# SCH_EspNowHub_2023-01-29.net
KiCad netlist of a schematic drawn in EasyEDA
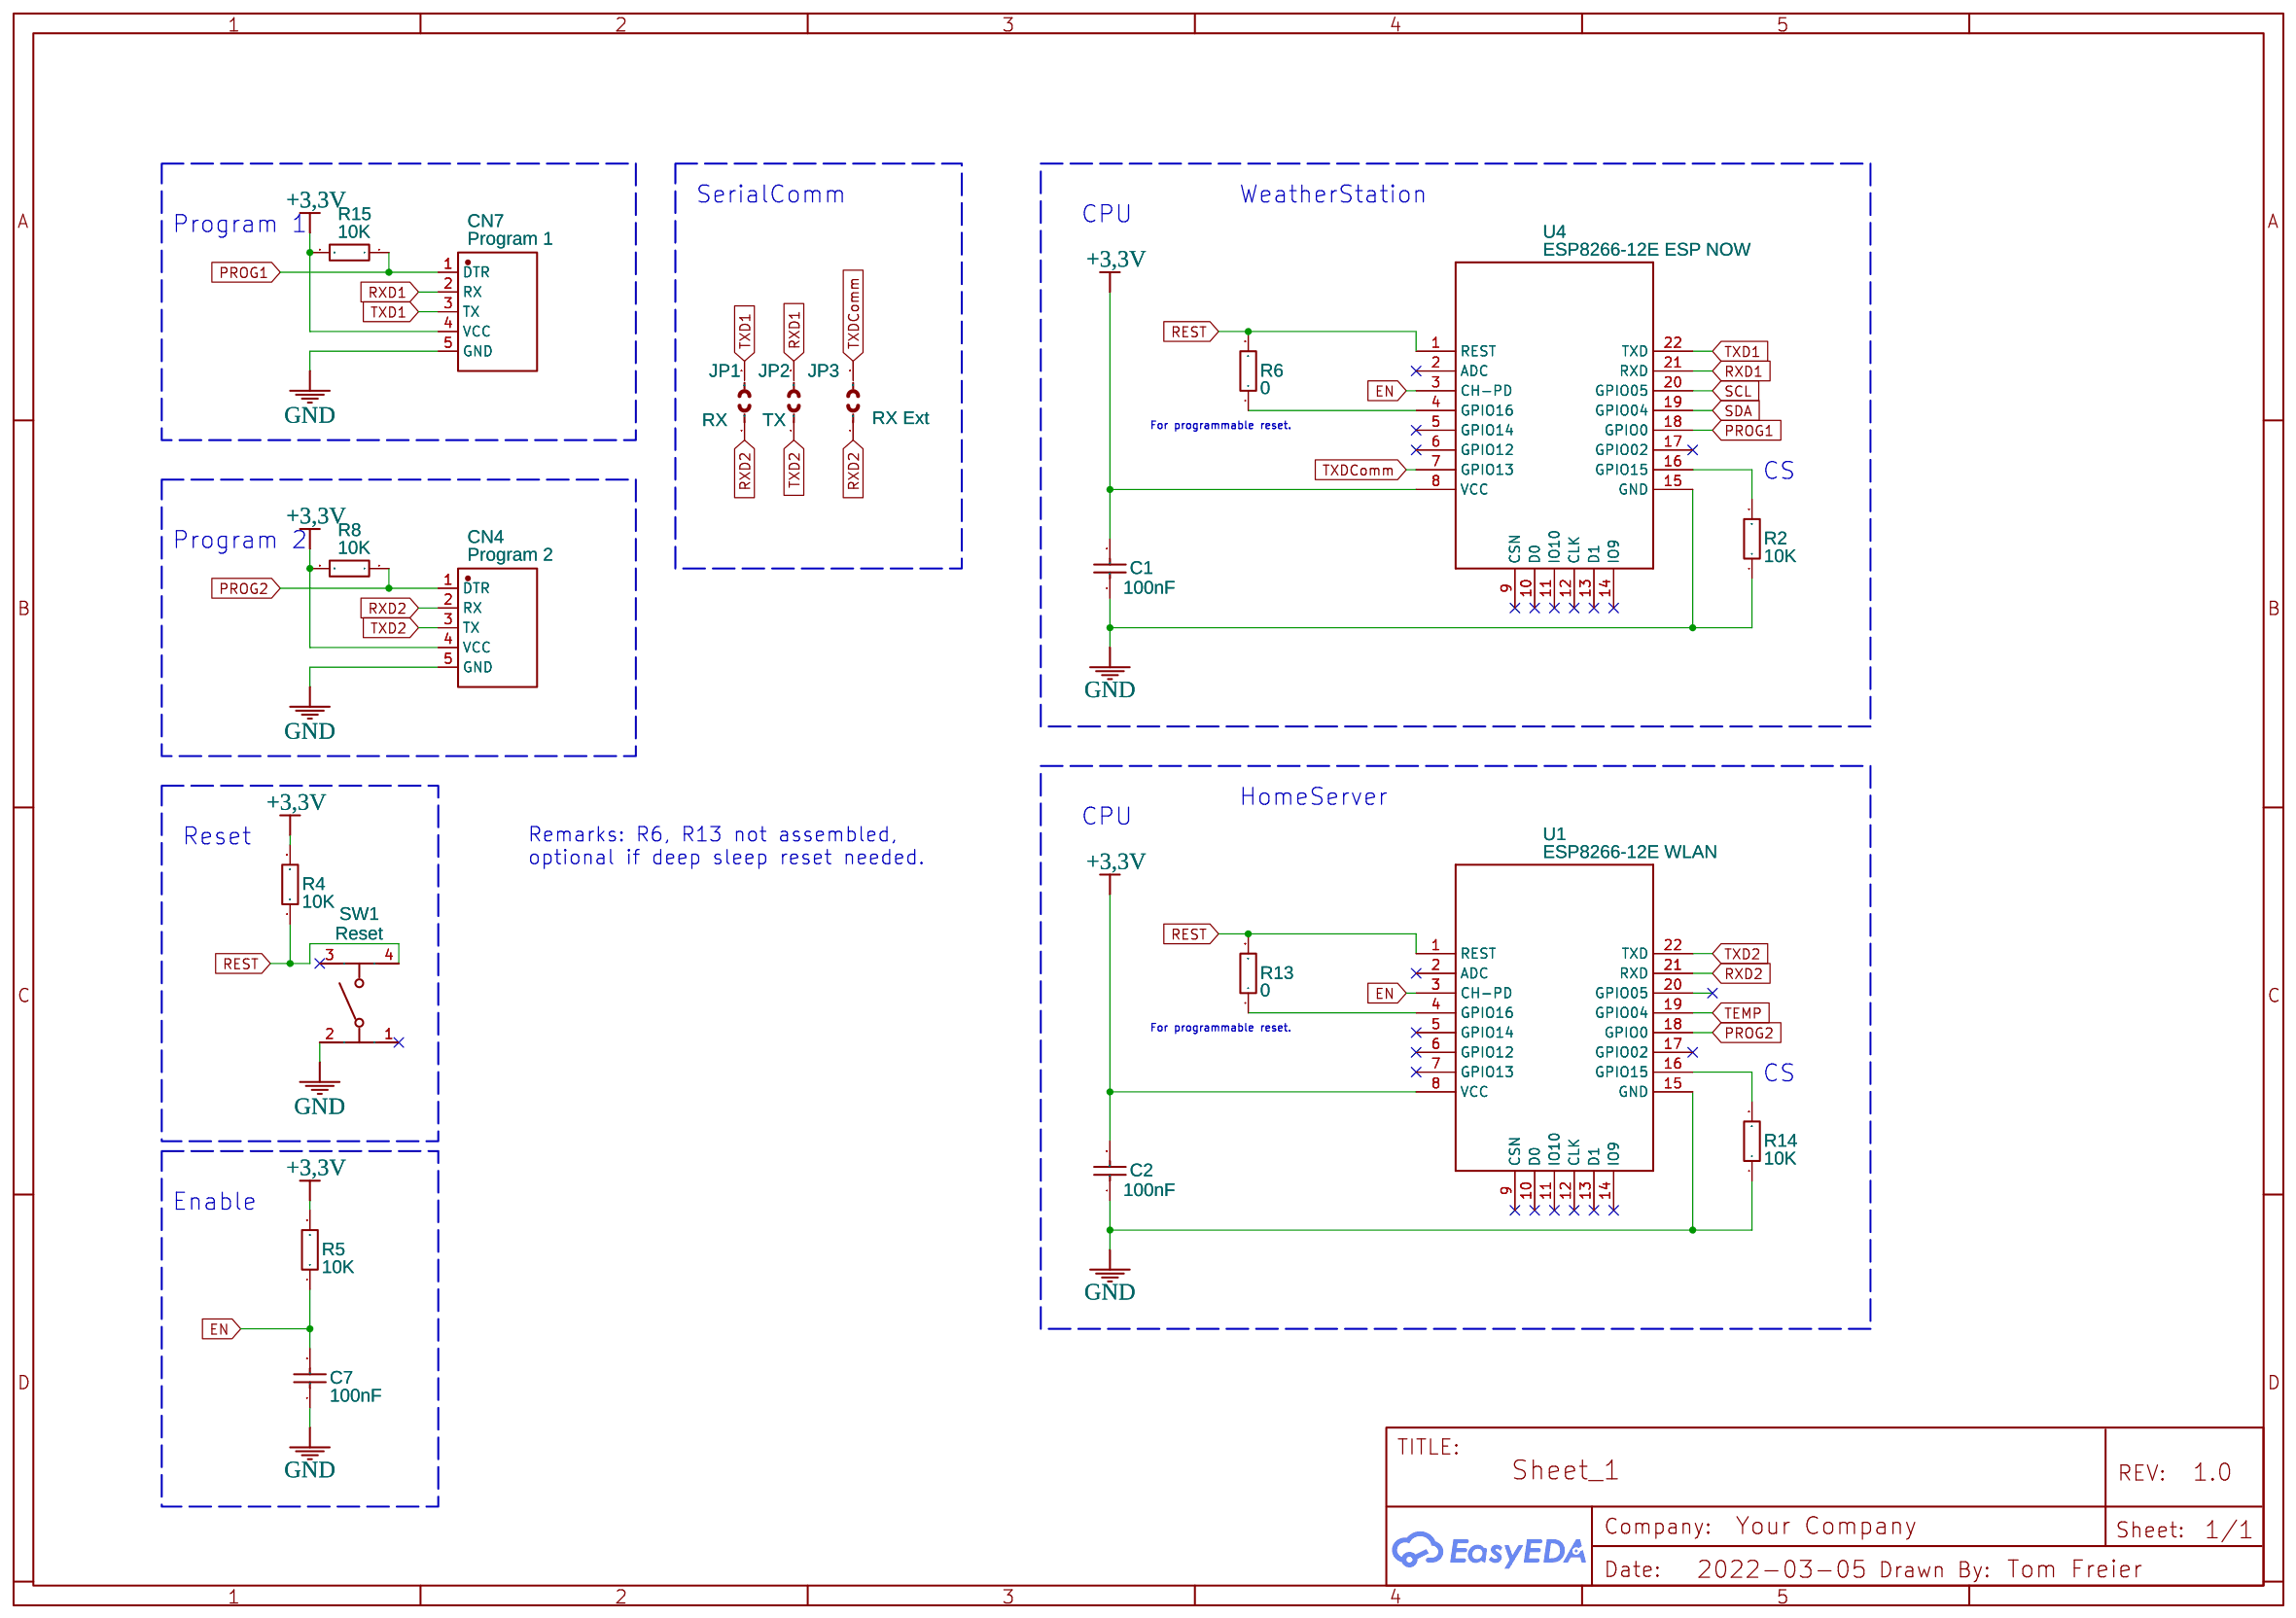
[diagram p0: CPU]
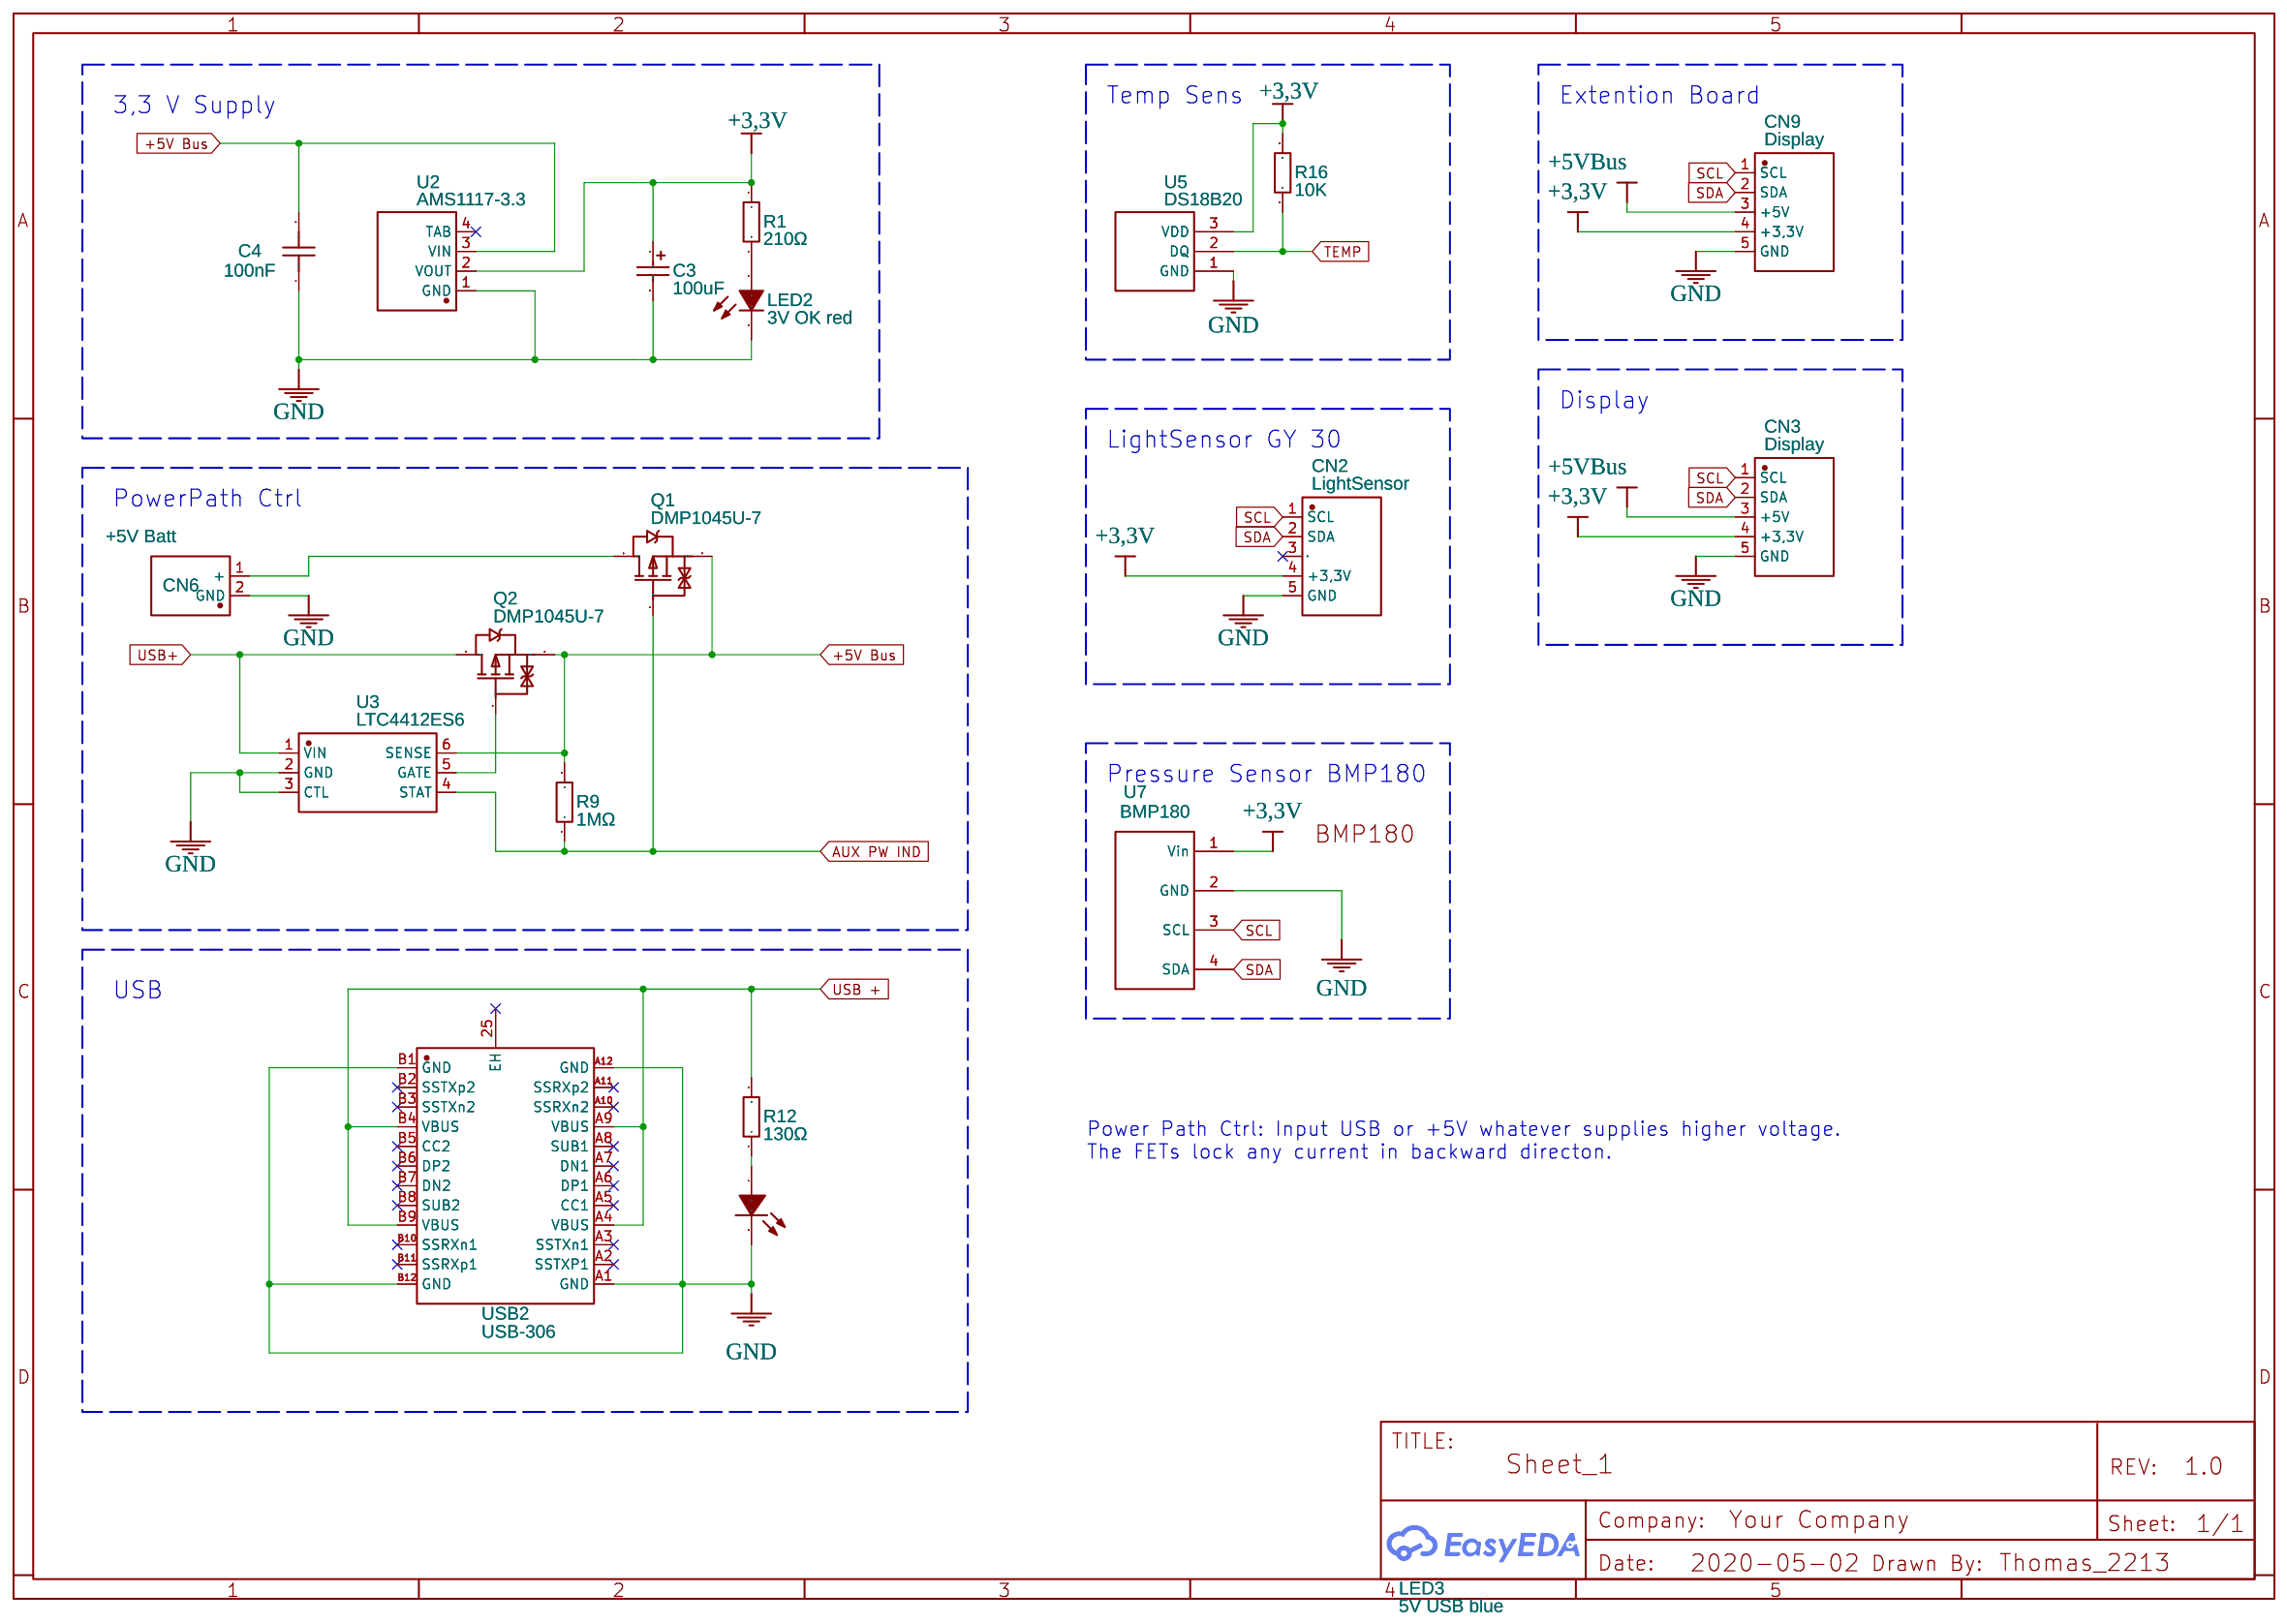
[diagram p1: Power Supply Sensor]

(export (version "E")
  (design (tool "Eeschema 10.0.6"))
  (components
    (comp (ref "C1")
      (value "100nF")
      (fields
        (field (name "BOM_Manufacturer Part") "CL10B104KC8NNNC")
        (field (name "BOM_Supplier Part") "C1688")
      )
      (libsource (lib "") (part "CL10B104JB8NNNC"))
    )
    (comp (ref "C2")
      (value "100nF")
      (fields
        (field (name "BOM_Manufacturer Part") "CL10B104KC8NNNC")
        (field (name "BOM_Supplier Part") "C1688")
      )
      (libsource (lib "") (part "CL10B104JB8NNNC"))
    )
    (comp (ref "C7")
      (value "100nF")
      (fields
        (field (name "BOM_Manufacturer Part") "CL10B104JB8NNNC")
        (field (name "BOM_Supplier Part") "C1688")
      )
      (libsource (lib "") (part "CL10B104JB8NNNC"))
    )
    (comp (ref "CN4")
      (value "Program 2")
      (fields (field (name "BOM_Supplier Part") "C161872"))
      (libsource (lib "") (part "B5B-XH-AM (LF)(SN)"))
    )
    (comp (ref "CN7")
      (value "Program 1")
      (fields (field (name "BOM_Supplier Part") "C161872"))
      (libsource (lib "") (part "B5B-XH-AM (LF)(SN)"))
    )
    (comp (ref "JP1") (value "RX") (libsource (lib "") (part "JumperOpenNoPaste")))
    (comp (ref "JP2") (value "TX") (libsource (lib "") (part "JumperOpenNoPaste")))
    (comp (ref "JP3") (value "RX Ext") (libsource (lib "") (part "JumperOpenNoPaste")))
    (comp (ref "R2")
      (value "10K")
      (fields
        (field (name "BOM_Manufacturer Part") "TC0325B1002T5E")
        (field (name "BOM_Supplier Part") "C39050")
      )
      (libsource (lib "") (part "TC0310B1002T5E"))
    )
    (comp (ref "R4")
      (value "10K")
      (fields
        (field (name "BOM_Manufacturer Part") "TC0310B1002T5E")
        (field (name "BOM_Supplier Part") "C190321")
      )
      (libsource (lib "") (part "TC0310B1002T5E"))
    )
    (comp (ref "R5")
      (value "10K")
      (fields
        (field (name "BOM_Manufacturer Part") "TC0310B1002T5E")
        (field (name "BOM_Supplier Part") "C190321")
      )
      (libsource (lib "") (part "TC0310B1002T5E"))
    )
    (comp (ref "R6")
      (value "0")
      (fields
        (field (name "BOM_Manufacturer Part") "0603WAJ0000T5E")
        (field (name "BOM_Supplier Part") "C15402")
      )
      (libsource (lib "") (part "0603WAJ0000T5E"))
    )
    (comp (ref "R8")
      (value "10K")
      (fields
        (field (name "BOM_Manufacturer Part") "TC0310B1002T5E")
        (field (name "BOM_Supplier Part") "C190321")
      )
      (libsource (lib "") (part "TC0310B1002T5E_1"))
    )
    (comp (ref "R13")
      (value "0")
      (fields
        (field (name "BOM_Manufacturer Part") "0603WAJ0000T5E")
        (field (name "BOM_Supplier Part") "C15402")
      )
      (libsource (lib "") (part "0603WAJ0000T5E"))
    )
    (comp (ref "R14")
      (value "10K")
      (fields
        (field (name "BOM_Manufacturer Part") "TC0325B1002T5E")
        (field (name "BOM_Supplier Part") "C39050")
      )
      (libsource (lib "") (part "TC0310B1002T5E"))
    )
    (comp (ref "R15")
      (value "10K")
      (fields
        (field (name "BOM_Manufacturer Part") "TC0310B1002T5E")
        (field (name "BOM_Supplier Part") "C190321")
      )
      (libsource (lib "") (part "TC0310B1002T5E_1"))
    )
    (comp (ref "SW1")
      (value "Reset")
      (fields
        (field (name "BOM_Manufacturer Part") "TL3301TF160QG/D310794")
        (field (name "BOM_Supplier Part") "C273532")
      )
      (libsource (lib "") (part "TL3301TF160QG/D310794"))
    )
    (comp (ref "U1")
      (value "ESP8266-12E WLAN")
      (fields
        (field (name "BOM_Manufacturer Part") "ESP8266-12E/ESP-12E")
        (field (name "BOM_Supplier Part") "317060015")
      )
      (libsource (lib "") (part "Unknown_780_-280"))
    )
    (comp (ref "U4")
      (value "ESP8266-12E ESP NOW")
      (fields
        (field (name "BOM_Manufacturer Part") "ESP8266-12E/ESP-12E")
        (field (name "BOM_Supplier Part") "317060015")
      )
      (libsource (lib "") (part "Unknown_780_-585"))
    )
    (comp (ref "C3")
      (value "100uF")
      (fields
        (field (name "BOM_Manufacturer Part") "CA45-D-16V-100UF-K")
        (field (name "BOM_Supplier Part") "C129274")
      )
      (libsource (lib "") (part "CA45-D-16V-100UF-K"))
    )
    (comp (ref "C4")
      (value "100nF")
      (fields
        (field (name "BOM_Manufacturer Part") "CL10B104KC8NNNC")
        (field (name "BOM_Supplier Part") "C1688")
      )
      (libsource (lib "") (part "CL10B104KC8NNNC"))
    )
    (comp (ref "CN2")
      (value "LightSensor")
      (fields (field (name "BOM_Supplier Part") "C161872"))
      (libsource (lib "") (part "B5B-XH-AM (LF)(SN)"))
    )
    (comp (ref "CN3")
      (value "Display")
      (fields (field (name "BOM_Supplier Part") "C161872"))
      (libsource (lib "") (part "B5B-XH-AM (LF)(SN)"))
    )
    (comp (ref "CN6")
      (value "+5V Batt")
      (fields (field (name "BOM_Supplier Part") "C161869"))
      (libsource (lib "") (part "B2B-XH-AM (LF)(SN)"))
    )
    (comp (ref "CN9")
      (value "Display")
      (fields (field (name "BOM_Supplier Part") "C161872"))
      (libsource (lib "") (part "B5B-XH-AM (LF)(SN)"))
    )
    (comp (ref "LED2")
      (value "3V OK red")
      (fields
        (field (name "BOM_Manufacturer Part") "17-21SURC/S530-A3/TR8")
        (field (name "BOM_Supplier Part") "C72037")
      )
      (libsource (lib "") (part "17-21SURC/S530-A3/TR8"))
    )
    (comp (ref "LED3")
      (value "5V USB blue")
      (fields
        (field (name "BOM_Manufacturer Part") "FC-2012UGK-520D5")
        (field (name "BOM_Supplier Part") "C84260")
      )
      (libsource (lib "") (part "FC-2012UGK-520D5"))
    )
    (comp (ref "Q1")
      (value "DMP1045U-7")
      (fields (field (name "BOM_Supplier Part") "C177033"))
      (libsource (lib "") (part "DMP1045U-7"))
    )
    (comp (ref "Q2")
      (value "DMP1045U-7")
      (fields (field (name "BOM_Supplier Part") "C177033"))
      (libsource (lib "") (part "DMP1045U-7"))
    )
    (comp (ref "R1")
      (value "210Ω")
      (fields
        (field (name "BOM_Manufacturer Part") "0603WAF2100T5E")
        (field (name "BOM_Supplier Part") "C22953")
      )
      (libsource (lib "") (part "0603WAF2100T5E"))
    )
    (comp (ref "R9")
      (value "1MΩ")
      (fields
        (field (name "BOM_Manufacturer Part") "0603WAF1004T5E")
        (field (name "BOM_Supplier Part") "C22935")
      )
      (libsource (lib "") (part "0603WAF1004T5E"))
    )
    (comp (ref "R12")
      (value "130Ω")
      (fields
        (field (name "BOM_Manufacturer Part") "0603WAF1300T5E")
        (field (name "BOM_Supplier Part") "C22796")
      )
      (libsource (lib "") (part "0603WAF1300T5E"))
    )
    (comp (ref "R16")
      (value "10K")
      (fields
        (field (name "BOM_Manufacturer Part") "TC0325B1002T5E")
        (field (name "BOM_Supplier Part") "C39050")
      )
      (libsource (lib "") (part "TC0310B1002T5E"))
    )
    (comp (ref "U2")
      (value "AMS1117-3.3")
      (fields (field (name "BOM_Supplier Part") "C498117"))
      (libsource (lib "") (part "AMS1117-3.3_C498117"))
    )
    (comp (ref "U3")
      (value "LTC4412ES6")
      (fields
        (field (name "BOM_Manufacturer Part") "LTC4412ES6#TRPBF")
        (field (name "BOM_Supplier Part") "C514442")
      )
      (libsource (lib "") (part "LTC4412ES6#TRPBF"))
    )
    (comp (ref "U5")
      (value "DS18B20")
      (fields (field (name "BOM_Manufacturer Part") "DS18B20+") (field (name "BOM_Supplier Part") "C9753"))
      (libsource (lib "") (part "Unknown_580_-695"))
    )
    (comp (ref "U7")
      (value "BMP180")
      (fields (field (name "BOM_Manufacturer Part") "PROJ_LIC Lib"))
      (libsource (lib "") (part "BMP180"))
    )
    (comp (ref "USB2")
      (value "USB-306")
      (fields (field (name "BOM_Supplier Part") "C309338"))
      (libsource (lib "") (part "USB-306"))
    )
  )
  (nets
    (net (code "1") (name "+3,3V") (class "Default")
      (node (ref "C1") (pin "2") (pinfunction "2_2") (pintype "input"))
      (node (ref "C2") (pin "2") (pinfunction "2_2") (pintype "input"))
      (node (ref "C3") (pin "1") (pinfunction "1_1") (pintype "input"))
      (node (ref "CN2") (pin "4") (pinfunction "+3,3V_4") (pintype "unspecified"))
      (node (ref "CN3") (pin "4") (pinfunction "+3,3V_4") (pintype "unspecified"))
      (node (ref "CN4") (pin "4") (pinfunction "VCC_4") (pintype "unspecified"))
      (node (ref "CN7") (pin "4") (pinfunction "VCC_4") (pintype "unspecified"))
      (node (ref "CN9") (pin "4") (pinfunction "+3,3V_4") (pintype "unspecified"))
      (node (ref "R1") (pin "1") (pinfunction "1_1") (pintype "input"))
      (node (ref "R15") (pin "2") (pinfunction "2_2") (pintype "unspecified"))
      (node (ref "R16") (pin "2") (pinfunction "2_2") (pintype "unspecified"))
      (node (ref "R4") (pin "2") (pinfunction "2_2") (pintype "unspecified"))
      (node (ref "R5") (pin "2") (pinfunction "2_2") (pintype "unspecified"))
      (node (ref "R8") (pin "2") (pinfunction "2_2") (pintype "unspecified"))
      (node (ref "U1") (pin "8") (pinfunction "VCC_8") (pintype "unspecified"))
      (node (ref "U2") (pin "2") (pinfunction "VOUT_2") (pintype "unspecified"))
      (node (ref "U4") (pin "8") (pinfunction "VCC_8") (pintype "unspecified"))
      (node (ref "U5") (pin "3") (pinfunction "VDD_3") (pintype "unspecified"))
      (node (ref "U7") (pin "1") (pinfunction "Vin_1") (pintype "input"))
    )
    (net (code "2") (name "+5V Bus") (class "Default")
      (node (ref "C4") (pin "2") (pinfunction "2_2") (pintype "unspecified"))
      (node (ref "Q1") (pin "2") (pinfunction "S_2") (pintype "unspecified"))
      (node (ref "Q2") (pin "2") (pinfunction "S_2") (pintype "unspecified"))
      (node (ref "R9") (pin "2") (pinfunction "2_2") (pintype "input"))
      (node (ref "U2") (pin "3") (pinfunction "VIN_3") (pintype "unspecified"))
      (node (ref "U3") (pin "6") (pinfunction "SENSE_6") (pintype "unspecified"))
    )
    (net (code "3") (name "+5VBus") (class "Default")
      (node (ref "CN3") (pin "3") (pinfunction "+5V_3") (pintype "unspecified"))
      (node (ref "CN9") (pin "3") (pinfunction "+5V_3") (pintype "unspecified"))
    )
    (net (code "4") (name "AUX PW IND") (class "Default")
      (node (ref "Q1") (pin "1") (pinfunction "G_1") (pintype "unspecified"))
      (node (ref "R9") (pin "1") (pinfunction "1_1") (pintype "input"))
      (node (ref "U3") (pin "4") (pinfunction "STAT_4") (pintype "unspecified"))
    )
    (net (code "5") (name "EN") (class "Default")
      (node (ref "C7") (pin "2") (pinfunction "2_2") (pintype "input"))
      (node (ref "R5") (pin "1") (pinfunction "1_1") (pintype "unspecified"))
      (node (ref "U1") (pin "3") (pinfunction "CH-PD_3") (pintype "unspecified"))
      (node (ref "U4") (pin "3") (pinfunction "CH-PD_3") (pintype "unspecified"))
    )
    (net (code "6") (name "GND") (class "Default")
      (node (ref "C1") (pin "1") (pinfunction "1_1") (pintype "input"))
      (node (ref "C2") (pin "1") (pinfunction "1_1") (pintype "input"))
      (node (ref "C3") (pin "2") (pinfunction "2_2") (pintype "input"))
      (node (ref "C4") (pin "1") (pinfunction "1_1") (pintype "unspecified"))
      (node (ref "C7") (pin "1") (pinfunction "1_1") (pintype "input"))
      (node (ref "CN2") (pin "5") (pinfunction "GND_5") (pintype "unspecified"))
      (node (ref "CN3") (pin "5") (pinfunction "GND_5") (pintype "unspecified"))
      (node (ref "CN4") (pin "5") (pinfunction "GND_5") (pintype "unspecified"))
      (node (ref "CN6") (pin "2") (pinfunction "GND_2") (pintype "unspecified"))
      (node (ref "CN7") (pin "5") (pinfunction "GND_5") (pintype "unspecified"))
      (node (ref "CN9") (pin "5") (pinfunction "GND_5") (pintype "unspecified"))
      (node (ref "LED2") (pin "2") (pinfunction "C_2") (pintype "input"))
      (node (ref "LED3") (pin "2") (pinfunction "K_2") (pintype "unspecified"))
      (node (ref "R14") (pin "1") (pinfunction "1_1") (pintype "unspecified"))
      (node (ref "R2") (pin "1") (pinfunction "1_1") (pintype "unspecified"))
      (node (ref "SW1") (pin "2") (pinfunction "2_2") (pintype "unspecified"))
      (node (ref "U1") (pin "15") (pinfunction "GND_15") (pintype "unspecified"))
      (node (ref "U2") (pin "1") (pinfunction "GND_1") (pintype "unspecified"))
      (node (ref "U3") (pin "2") (pinfunction "GND_2") (pintype "unspecified"))
      (node (ref "U3") (pin "3") (pinfunction "CTL_3") (pintype "unspecified"))
      (node (ref "U4") (pin "15") (pinfunction "GND_15") (pintype "unspecified"))
      (node (ref "U5") (pin "1") (pinfunction "GND_1") (pintype "unspecified"))
      (node (ref "U7") (pin "2") (pinfunction "GND_2") (pintype "unspecified"))
      (node (ref "USB2") (pin "A1") (pinfunction "GND_A1") (pintype "unspecified"))
      (node (ref "USB2") (pin "A12") (pinfunction "GND_A12") (pintype "unspecified"))
      (node (ref "USB2") (pin "B1") (pinfunction "GND_B1") (pintype "unspecified"))
      (node (ref "USB2") (pin "B12") (pinfunction "GND_B12") (pintype "unspecified"))
    )
    (net (code "7") (name "Net-(CN6-+)") (class "Default")
      (node (ref "CN6") (pin "1") (pinfunction "+_1") (pintype "unspecified"))
      (node (ref "Q1") (pin "3") (pinfunction "D_3") (pintype "unspecified"))
    )
    (net (code "8") (name "Net-(LED2-A)") (class "Default")
      (node (ref "LED2") (pin "1") (pinfunction "A_1") (pintype "input"))
      (node (ref "R1") (pin "2") (pinfunction "2_2") (pintype "input"))
    )
    (net (code "9") (name "Net-(LED3-A)") (class "Default")
      (node (ref "LED3") (pin "1") (pinfunction "A_1") (pintype "unspecified"))
      (node (ref "R12") (pin "1") (pinfunction "1_1") (pintype "input"))
    )
    (net (code "10") (name "Net-(Q2-G)") (class "Default")
      (node (ref "Q2") (pin "1") (pinfunction "G_1") (pintype "unspecified"))
      (node (ref "U3") (pin "5") (pinfunction "GATE_5") (pintype "unspecified"))
    )
    (net (code "11") (name "Net-(U1-GPIO15)") (class "Default")
      (node (ref "R14") (pin "2") (pinfunction "2_2") (pintype "unspecified"))
      (node (ref "U1") (pin "16") (pinfunction "GPIO15_16") (pintype "unspecified"))
    )
    (net (code "12") (name "Net-(U1-GPIO16)") (class "Default")
      (node (ref "R13") (pin "1") (pinfunction "1_1") (pintype "input"))
      (node (ref "U1") (pin "4") (pinfunction "GPIO16_4") (pintype "unspecified"))
    )
    (net (code "13") (name "Net-(U4-GPIO15)") (class "Default")
      (node (ref "R2") (pin "2") (pinfunction "2_2") (pintype "unspecified"))
      (node (ref "U4") (pin "16") (pinfunction "GPIO15_16") (pintype "unspecified"))
    )
    (net (code "14") (name "Net-(U4-GPIO16)") (class "Default")
      (node (ref "R6") (pin "1") (pinfunction "1_1") (pintype "input"))
      (node (ref "U4") (pin "4") (pinfunction "GPIO16_4") (pintype "unspecified"))
    )
    (net (code "15") (name "PROG1") (class "Default")
      (node (ref "CN7") (pin "1") (pinfunction "DTR_1") (pintype "unspecified"))
      (node (ref "R15") (pin "1") (pinfunction "1_1") (pintype "unspecified"))
      (node (ref "U4") (pin "18") (pinfunction "GPIO0_18") (pintype "unspecified"))
    )
    (net (code "16") (name "PROG2") (class "Default")
      (node (ref "CN4") (pin "1") (pinfunction "DTR_1") (pintype "unspecified"))
      (node (ref "R8") (pin "1") (pinfunction "1_1") (pintype "unspecified"))
      (node (ref "U1") (pin "18") (pinfunction "GPIO0_18") (pintype "unspecified"))
    )
    (net (code "17") (name "REST") (class "Default")
      (node (ref "R13") (pin "2") (pinfunction "2_2") (pintype "input"))
      (node (ref "R4") (pin "1") (pinfunction "1_1") (pintype "unspecified"))
      (node (ref "R6") (pin "2") (pinfunction "2_2") (pintype "input"))
      (node (ref "SW1") (pin "4") (pinfunction "4_4") (pintype "unspecified"))
      (node (ref "U1") (pin "1") (pinfunction "REST_1") (pintype "unspecified"))
      (node (ref "U4") (pin "1") (pinfunction "REST_1") (pintype "unspecified"))
    )
    (net (code "18") (name "RXD1") (class "Default")
      (node (ref "CN7") (pin "2") (pinfunction "RX_2") (pintype "unspecified"))
      (node (ref "JP2") (pin "2") (pinfunction "2_2") (pintype "bidirectional"))
      (node (ref "U4") (pin "21") (pinfunction "RXD_21") (pintype "unspecified"))
    )
    (net (code "19") (name "RXD2") (class "Default")
      (node (ref "CN4") (pin "2") (pinfunction "RX_2") (pintype "unspecified"))
      (node (ref "JP1") (pin "1") (pinfunction "1_1") (pintype "bidirectional"))
      (node (ref "JP3") (pin "1") (pinfunction "1_1") (pintype "bidirectional"))
      (node (ref "U1") (pin "21") (pinfunction "RXD_21") (pintype "unspecified"))
    )
    (net (code "20") (name "SCL") (class "Default")
      (node (ref "CN2") (pin "1") (pinfunction "SCL_1") (pintype "unspecified"))
      (node (ref "CN3") (pin "1") (pinfunction "SCL_1") (pintype "unspecified"))
      (node (ref "CN9") (pin "1") (pinfunction "SCL_1") (pintype "unspecified"))
      (node (ref "U4") (pin "20") (pinfunction "GPIO05_20") (pintype "unspecified"))
      (node (ref "U7") (pin "3") (pinfunction "SCL_3") (pintype "unspecified"))
    )
    (net (code "21") (name "SDA") (class "Default")
      (node (ref "CN2") (pin "2") (pinfunction "SDA_2") (pintype "unspecified"))
      (node (ref "CN3") (pin "2") (pinfunction "SDA_2") (pintype "unspecified"))
      (node (ref "CN9") (pin "2") (pinfunction "SDA_2") (pintype "unspecified"))
      (node (ref "U4") (pin "19") (pinfunction "GPIO04_19") (pintype "unspecified"))
      (node (ref "U7") (pin "4") (pinfunction "SDA_4") (pintype "unspecified"))
    )
    (net (code "22") (name "TEMP") (class "Default")
      (node (ref "R16") (pin "1") (pinfunction "1_1") (pintype "unspecified"))
      (node (ref "U1") (pin "19") (pinfunction "GPIO04_19") (pintype "unspecified"))
      (node (ref "U5") (pin "2") (pinfunction "DQ_2") (pintype "unspecified"))
    )
    (net (code "23") (name "TXD1") (class "Default")
      (node (ref "CN7") (pin "3") (pinfunction "TX_3") (pintype "unspecified"))
      (node (ref "JP1") (pin "2") (pinfunction "2_2") (pintype "bidirectional"))
      (node (ref "U4") (pin "22") (pinfunction "TXD_22") (pintype "unspecified"))
    )
    (net (code "24") (name "TXD2") (class "Default")
      (node (ref "CN4") (pin "3") (pinfunction "TX_3") (pintype "unspecified"))
      (node (ref "JP2") (pin "1") (pinfunction "1_1") (pintype "bidirectional"))
      (node (ref "U1") (pin "22") (pinfunction "TXD_22") (pintype "unspecified"))
    )
    (net (code "25") (name "TXDComm") (class "Default")
      (node (ref "JP3") (pin "2") (pinfunction "2_2") (pintype "bidirectional"))
      (node (ref "U4") (pin "7") (pinfunction "GPIO13_7") (pintype "unspecified"))
    )
    (net (code "26") (name "USB +") (class "Default")
      (node (ref "R12") (pin "2") (pinfunction "2_2") (pintype "input"))
      (node (ref "USB2") (pin "A4") (pinfunction "VBUS_A4") (pintype "unspecified"))
      (node (ref "USB2") (pin "A9") (pinfunction "VBUS_A9") (pintype "unspecified"))
      (node (ref "USB2") (pin "B4") (pinfunction "VBUS_B4") (pintype "unspecified"))
      (node (ref "USB2") (pin "B9") (pinfunction "VBUS_B9") (pintype "unspecified"))
    )
    (net (code "27") (name "USB+") (class "Default")
      (node (ref "Q2") (pin "3") (pinfunction "D_3") (pintype "unspecified"))
      (node (ref "U3") (pin "1") (pinfunction "VIN_1") (pintype "unspecified"))
    )
    (net (code "28") (name "unconnected-(CN2-+5V-Pad3)") (class "Default")
      (node (ref "CN2") (pin "3") (pinfunction "+5V_3") (pintype "unspecified+no_connect"))
    )
    (net (code "29") (name "unconnected-(SW1-Pad1)") (class "Default")
      (node (ref "SW1") (pin "1") (pinfunction "1_1") (pintype "unspecified+no_connect"))
    )
    (net (code "30") (name "unconnected-(SW1-Pad3)") (class "Default")
      (node (ref "SW1") (pin "3") (pinfunction "3_3") (pintype "unspecified+no_connect"))
    )
    (net (code "31") (name "unconnected-(U1-ADC-Pad2)") (class "Default")
      (node (ref "U1") (pin "2") (pinfunction "ADC_2") (pintype "unspecified+no_connect"))
    )
    (net (code "32") (name "unconnected-(U1-CLK-Pad12)") (class "Default")
      (node (ref "U1") (pin "12") (pinfunction "CLK_12") (pintype "unspecified+no_connect"))
    )
    (net (code "33") (name "unconnected-(U1-CSN-Pad9)") (class "Default")
      (node (ref "U1") (pin "9") (pinfunction "CSN_9") (pintype "unspecified+no_connect"))
    )
    (net (code "34") (name "unconnected-(U1-D0-Pad10)") (class "Default")
      (node (ref "U1") (pin "10") (pinfunction "D0_10") (pintype "unspecified+no_connect"))
    )
    (net (code "35") (name "unconnected-(U1-D1-Pad13)") (class "Default")
      (node (ref "U1") (pin "13") (pinfunction "D1_13") (pintype "unspecified+no_connect"))
    )
    (net (code "36") (name "unconnected-(U1-GPIO02-Pad17)") (class "Default")
      (node (ref "U1") (pin "17") (pinfunction "GPIO02_17") (pintype "unspecified+no_connect"))
    )
    (net (code "37") (name "unconnected-(U1-GPIO05-Pad20)") (class "Default")
      (node (ref "U1") (pin "20") (pinfunction "GPIO05_20") (pintype "unspecified+no_connect"))
    )
    (net (code "38") (name "unconnected-(U1-GPIO12-Pad6)") (class "Default")
      (node (ref "U1") (pin "6") (pinfunction "GPIO12_6") (pintype "unspecified+no_connect"))
    )
    (net (code "39") (name "unconnected-(U1-GPIO13-Pad7)") (class "Default")
      (node (ref "U1") (pin "7") (pinfunction "GPIO13_7") (pintype "unspecified+no_connect"))
    )
    (net (code "40") (name "unconnected-(U1-GPIO14-Pad5)") (class "Default")
      (node (ref "U1") (pin "5") (pinfunction "GPIO14_5") (pintype "unspecified+no_connect"))
    )
    (net (code "41") (name "unconnected-(U1-IO9-Pad14)") (class "Default")
      (node (ref "U1") (pin "14") (pinfunction "IO9_14") (pintype "unspecified+no_connect"))
    )
    (net (code "42") (name "unconnected-(U1-IO10-Pad11)") (class "Default")
      (node (ref "U1") (pin "11") (pinfunction "IO10_11") (pintype "unspecified+no_connect"))
    )
    (net (code "43") (name "unconnected-(U2-TAB-Pad4)") (class "Default")
      (node (ref "U2") (pin "4") (pinfunction "TAB_4") (pintype "unspecified+no_connect"))
    )
    (net (code "44") (name "unconnected-(U4-ADC-Pad2)") (class "Default")
      (node (ref "U4") (pin "2") (pinfunction "ADC_2") (pintype "unspecified+no_connect"))
    )
    (net (code "45") (name "unconnected-(U4-CLK-Pad12)") (class "Default")
      (node (ref "U4") (pin "12") (pinfunction "CLK_12") (pintype "unspecified+no_connect"))
    )
    (net (code "46") (name "unconnected-(U4-CSN-Pad9)") (class "Default")
      (node (ref "U4") (pin "9") (pinfunction "CSN_9") (pintype "unspecified+no_connect"))
    )
    (net (code "47") (name "unconnected-(U4-D0-Pad10)") (class "Default")
      (node (ref "U4") (pin "10") (pinfunction "D0_10") (pintype "unspecified+no_connect"))
    )
    (net (code "48") (name "unconnected-(U4-D1-Pad13)") (class "Default")
      (node (ref "U4") (pin "13") (pinfunction "D1_13") (pintype "unspecified+no_connect"))
    )
    (net (code "49") (name "unconnected-(U4-GPIO02-Pad17)") (class "Default")
      (node (ref "U4") (pin "17") (pinfunction "GPIO02_17") (pintype "unspecified+no_connect"))
    )
    (net (code "50") (name "unconnected-(U4-GPIO12-Pad6)") (class "Default")
      (node (ref "U4") (pin "6") (pinfunction "GPIO12_6") (pintype "unspecified+no_connect"))
    )
    (net (code "51") (name "unconnected-(U4-GPIO14-Pad5)") (class "Default")
      (node (ref "U4") (pin "5") (pinfunction "GPIO14_5") (pintype "unspecified+no_connect"))
    )
    (net (code "52") (name "unconnected-(U4-IO9-Pad14)") (class "Default")
      (node (ref "U4") (pin "14") (pinfunction "IO9_14") (pintype "unspecified+no_connect"))
    )
    (net (code "53") (name "unconnected-(U4-IO10-Pad11)") (class "Default")
      (node (ref "U4") (pin "11") (pinfunction "IO10_11") (pintype "unspecified+no_connect"))
    )
    (net (code "54") (name "unconnected-(USB2-CC1-PadA5)") (class "Default")
      (node (ref "USB2") (pin "A5") (pinfunction "CC1_A5") (pintype "unspecified+no_connect"))
    )
    (net (code "55") (name "unconnected-(USB2-CC2-PadB5)") (class "Default")
      (node (ref "USB2") (pin "B5") (pinfunction "CC2_B5") (pintype "unspecified+no_connect"))
    )
    (net (code "56") (name "unconnected-(USB2-DN1-PadA7)") (class "Default")
      (node (ref "USB2") (pin "A7") (pinfunction "DN1_A7") (pintype "unspecified+no_connect"))
    )
    (net (code "57") (name "unconnected-(USB2-DN2-PadB7)") (class "Default")
      (node (ref "USB2") (pin "B7") (pinfunction "DN2_B7") (pintype "unspecified+no_connect"))
    )
    (net (code "58") (name "unconnected-(USB2-DP1-PadA6)") (class "Default")
      (node (ref "USB2") (pin "A6") (pinfunction "DP1_A6") (pintype "unspecified+no_connect"))
    )
    (net (code "59") (name "unconnected-(USB2-DP2-PadB6)") (class "Default")
      (node (ref "USB2") (pin "B6") (pinfunction "DP2_B6") (pintype "unspecified+no_connect"))
    )
    (net (code "60") (name "unconnected-(USB2-EH-Pad25)") (class "Default")
      (node (ref "USB2") (pin "25") (pinfunction "EH_25") (pintype "unspecified+no_connect"))
    )
    (net (code "61") (name "unconnected-(USB2-SSRXn1-PadB10)") (class "Default")
      (node (ref "USB2") (pin "B10") (pinfunction "SSRXn1_B10") (pintype "unspecified+no_connect"))
    )
    (net (code "62") (name "unconnected-(USB2-SSRXn2-PadA10)") (class "Default")
      (node (ref "USB2") (pin "A10") (pinfunction "SSRXn2_A10") (pintype "unspecified+no_connect"))
    )
    (net (code "63") (name "unconnected-(USB2-SSRXp1-PadB11)") (class "Default")
      (node (ref "USB2") (pin "B11") (pinfunction "SSRXp1_B11") (pintype "unspecified+no_connect"))
    )
    (net (code "64") (name "unconnected-(USB2-SSRXp2-PadA11)") (class "Default")
      (node (ref "USB2") (pin "A11") (pinfunction "SSRXp2_A11") (pintype "unspecified+no_connect"))
    )
    (net (code "65") (name "unconnected-(USB2-SSTXP1-PadA2)") (class "Default")
      (node (ref "USB2") (pin "A2") (pinfunction "SSTXP1_A2") (pintype "unspecified+no_connect"))
    )
    (net (code "66") (name "unconnected-(USB2-SSTXn1-PadA3)") (class "Default")
      (node (ref "USB2") (pin "A3") (pinfunction "SSTXn1_A3") (pintype "unspecified+no_connect"))
    )
    (net (code "67") (name "unconnected-(USB2-SSTXn2-PadB3)") (class "Default")
      (node (ref "USB2") (pin "B3") (pinfunction "SSTXn2_B3") (pintype "unspecified+no_connect"))
    )
    (net (code "68") (name "unconnected-(USB2-SSTXp2-PadB2)") (class "Default")
      (node (ref "USB2") (pin "B2") (pinfunction "SSTXp2_B2") (pintype "unspecified+no_connect"))
    )
    (net (code "69") (name "unconnected-(USB2-SUB1-PadA8)") (class "Default")
      (node (ref "USB2") (pin "A8") (pinfunction "SUB1_A8") (pintype "unspecified+no_connect"))
    )
    (net (code "70") (name "unconnected-(USB2-SUB2-PadB8)") (class "Default")
      (node (ref "USB2") (pin "B8") (pinfunction "SUB2_B8") (pintype "unspecified+no_connect"))
    )
  )
)
